# PART1.net
KiCad netlist of a schematic drawn in Altium Designer
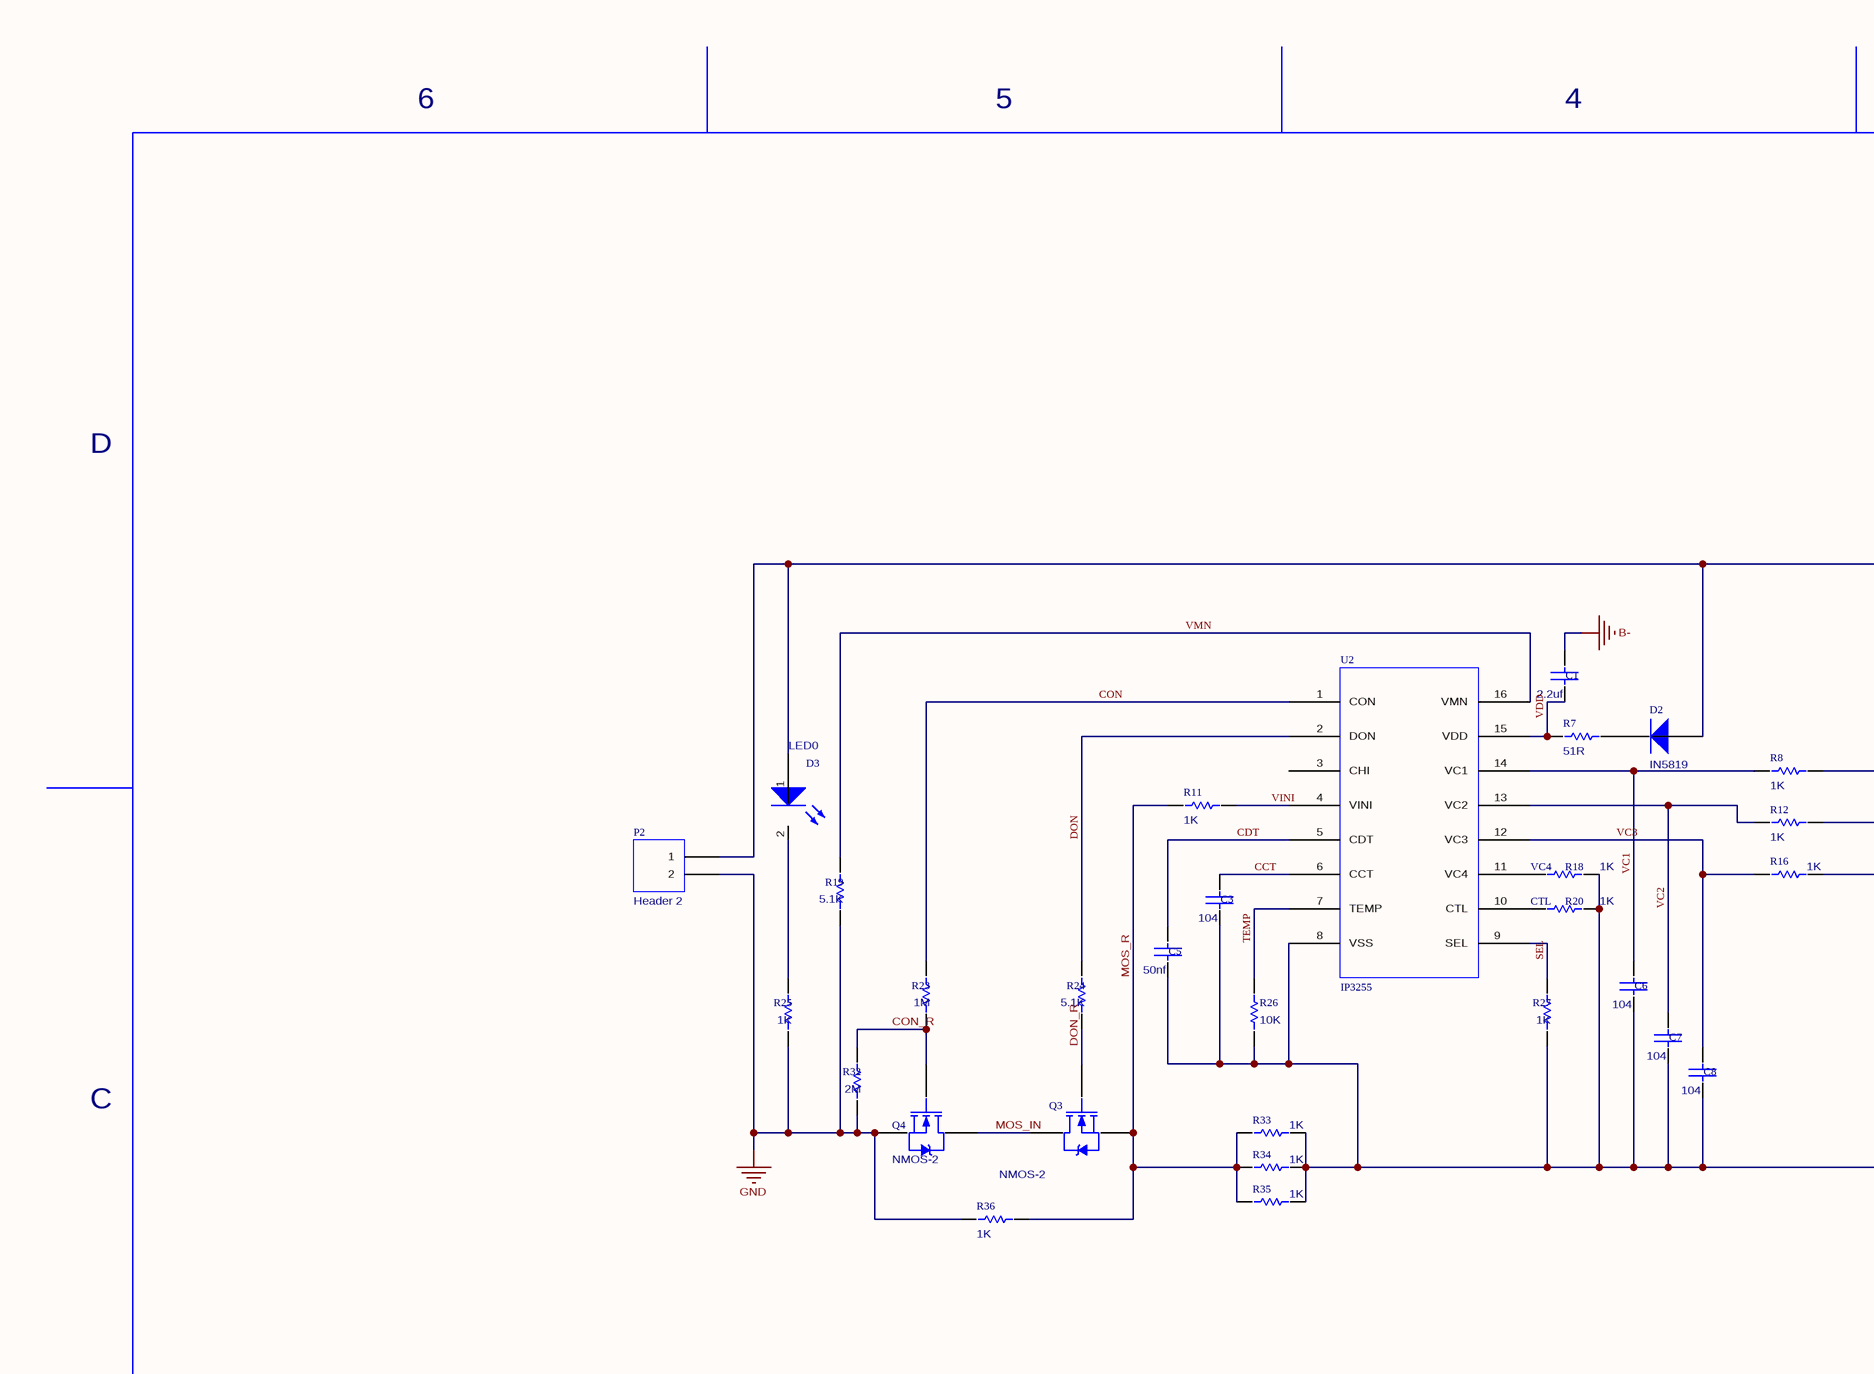
[diagram p0: PART1.SchDoc, top left]
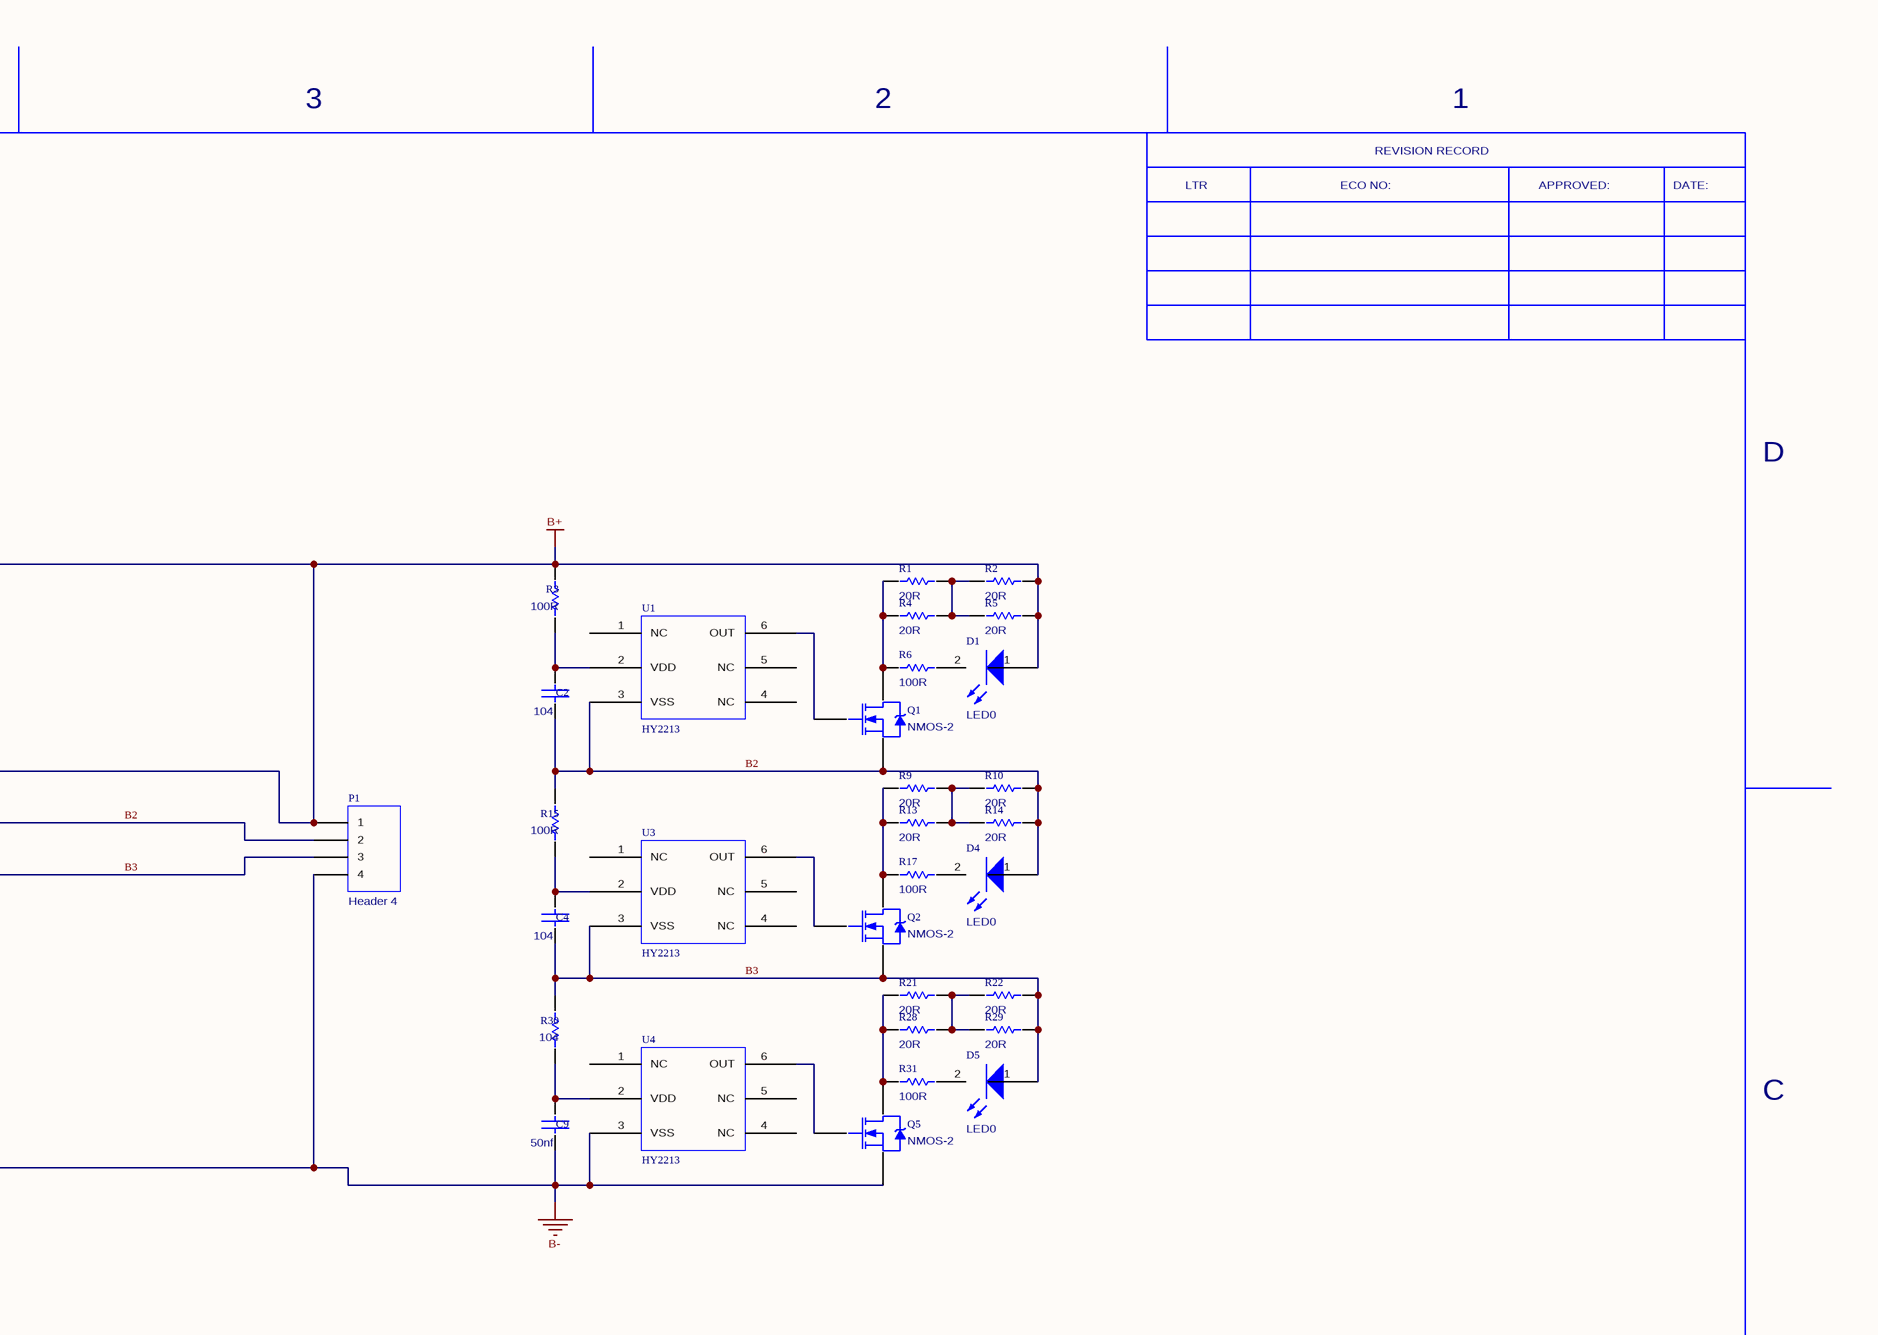
[diagram p1: PART1.SchDoc, top right]
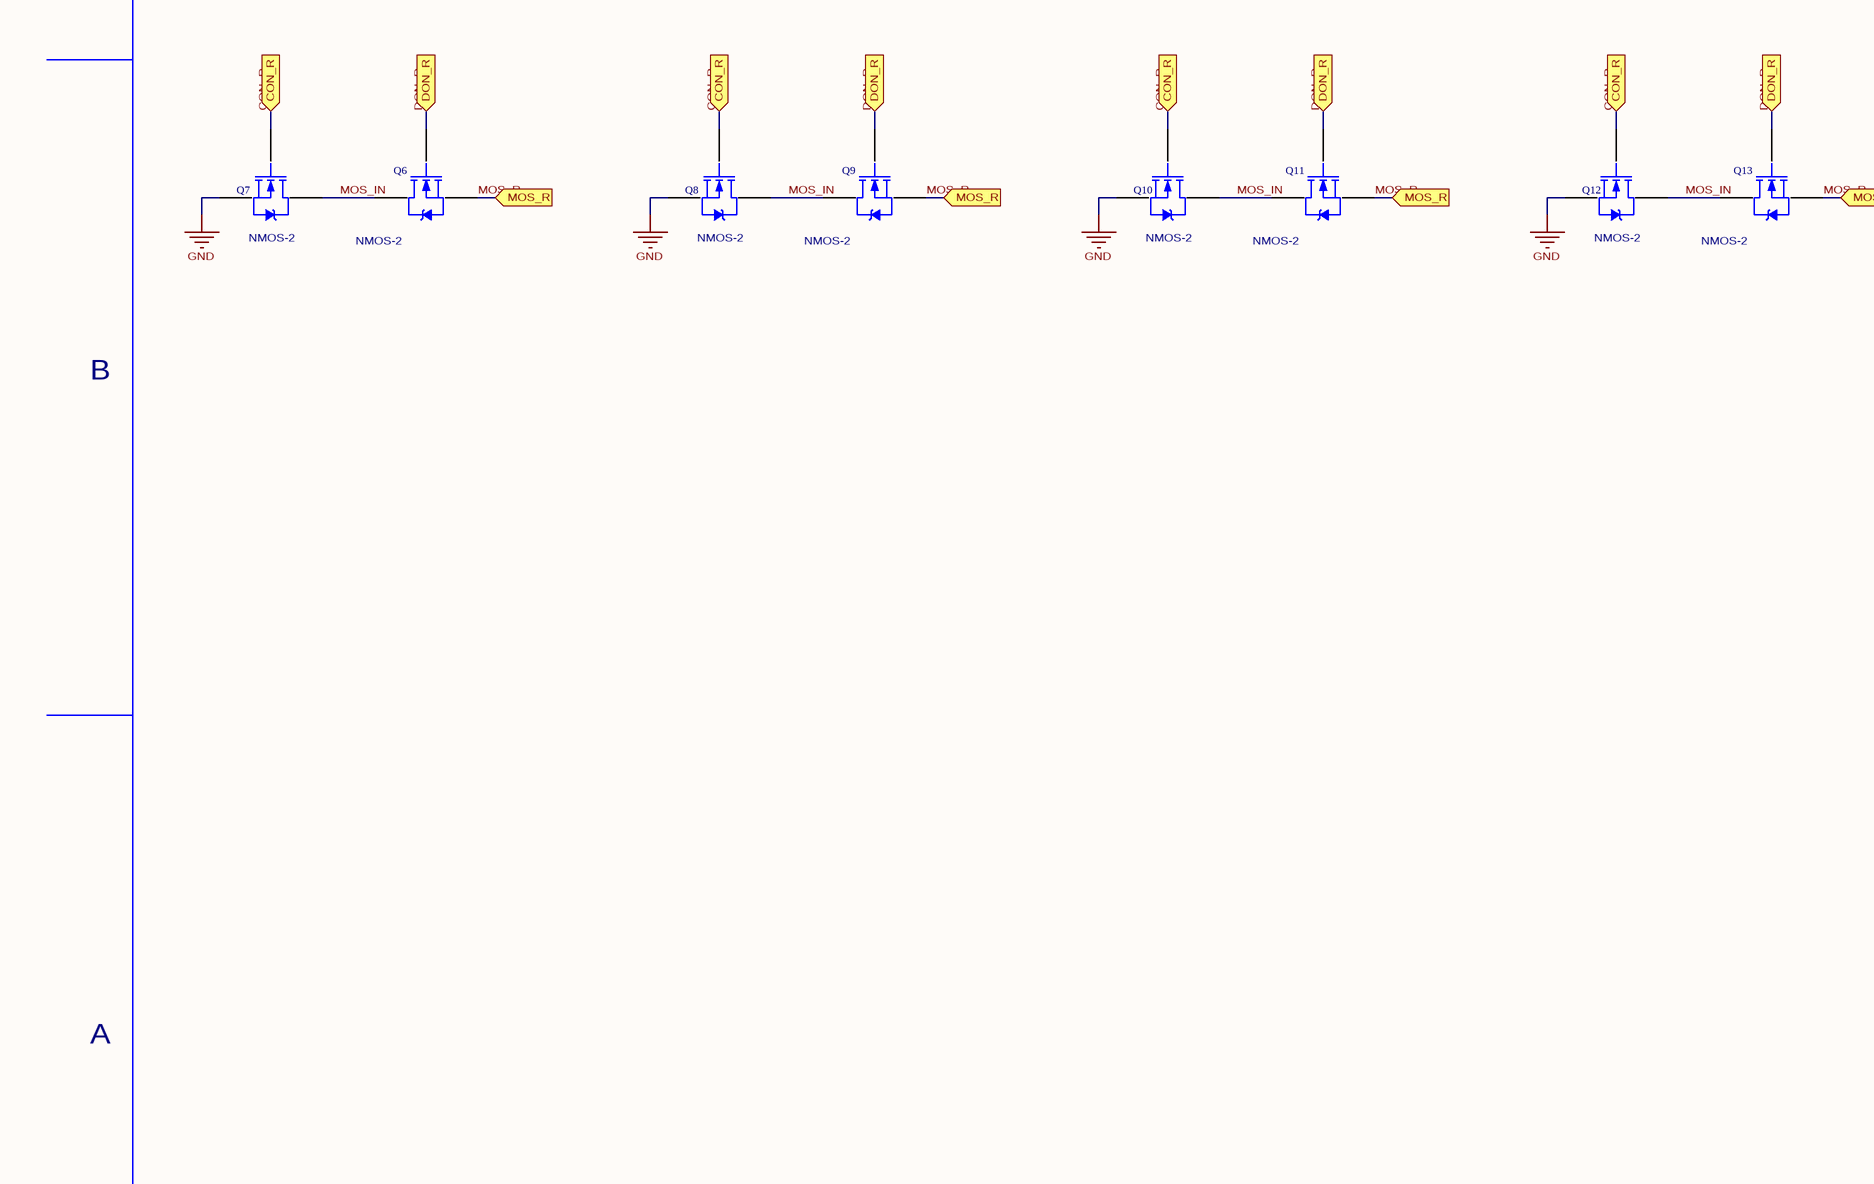
[diagram p2: PART1.SchDoc, bottom left]
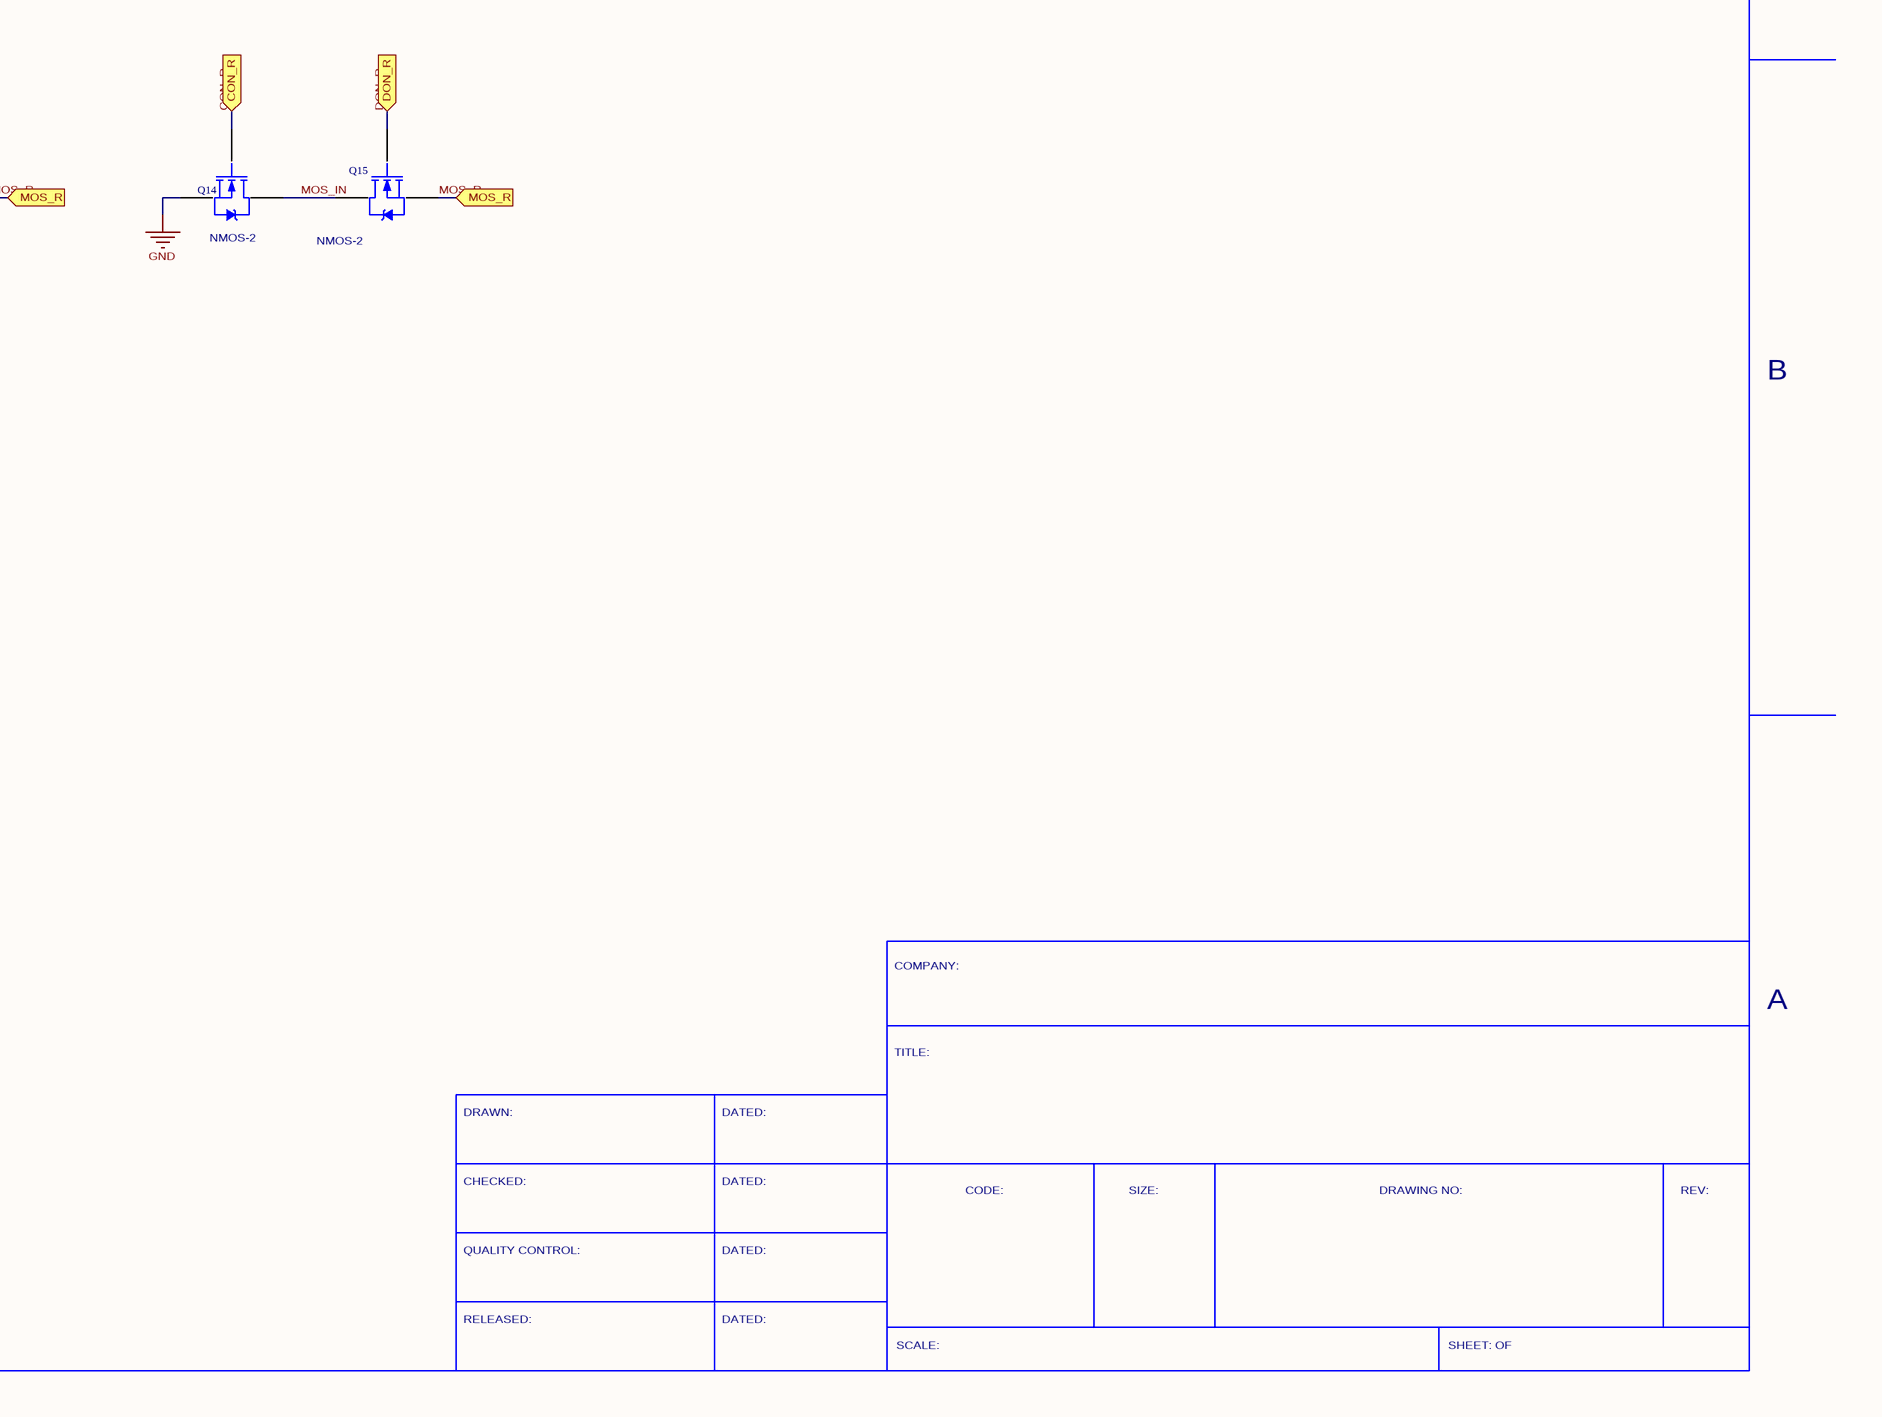
[diagram p3: PART1.SchDoc, bottom right]

(export (version "E")
  (design (tool "Eeschema 10.0.6"))
  (components
    (comp (ref "C1")
      (value "2.2uf")
      (footprint "0805C")
      (description "Capacitor")
      (fields (field (name "Comment") "CAP") (field (name "PUBLISHER") "Altium Limited"))
      (libsource (lib "*") (part "CAP"))
    )
    (comp (ref "C2")
      (value "104")
      (footprint "0603C")
      (description "Capacitor")
      (fields (field (name "Comment") "CAP") (field (name "PUBLISHER") "Altium Limited"))
      (libsource (lib "*") (part "CAP"))
    )
    (comp (ref "C3")
      (value "104")
      (footprint "0805C")
      (description "Capacitor")
      (fields (field (name "Comment") "CAP") (field (name "PUBLISHER") "Altium Limited"))
      (libsource (lib "*") (part "CAP"))
    )
    (comp (ref "C4")
      (value "104")
      (footprint "0603C")
      (description "Capacitor")
      (fields (field (name "Comment") "CAP") (field (name "PUBLISHER") "Altium Limited"))
      (libsource (lib "*") (part "CAP"))
    )
    (comp (ref "C5")
      (value "50nf")
      (footprint "0805C")
      (description "Capacitor")
      (fields (field (name "Comment") "CAP") (field (name "PUBLISHER") "Altium Limited"))
      (libsource (lib "*") (part "CAP"))
    )
    (comp (ref "C6")
      (value "104")
      (footprint "0603C")
      (description "Capacitor")
      (fields (field (name "Comment") "CAP") (field (name "PUBLISHER") "Altium Limited"))
      (libsource (lib "*") (part "CAP"))
    )
    (comp (ref "C7")
      (value "104")
      (footprint "0603C")
      (description "Capacitor")
      (fields (field (name "Comment") "CAP") (field (name "PUBLISHER") "Altium Limited"))
      (libsource (lib "*") (part "CAP"))
    )
    (comp (ref "C8")
      (value "104")
      (footprint "0603C")
      (description "Capacitor")
      (fields (field (name "Comment") "CAP") (field (name "PUBLISHER") "Altium Limited"))
      (libsource (lib "*") (part "CAP"))
    )
    (comp (ref "C9")
      (value "50nf")
      (footprint "0603C")
      (description "Capacitor")
      (fields (field (name "Comment") "CAP") (field (name "PUBLISHER") "Altium Limited"))
      (libsource (lib "*") (part "CAP"))
    )
    (comp (ref "D1")
      (value "LED0")
      (footprint "0805D")
      (description "Typical INFRARED GaAs LED")
      (fields (field (name "PUBLISHER") "Altium Limited"))
      (libsource (lib "*") (part "LED0"))
    )
    (comp (ref "D2")
      (value "DIODE_1N4001")
      (footprint "SOD123")
      (description "1 Amp General Purpose Rectifier")
      (fields (field (name "PUBLISHER") "Altium Limited"))
      (libsource (lib "*") (part "DIODE_1N4001"))
    )
    (comp (ref "D3")
      (value "LED0")
      (footprint "0805D")
      (description "Typical INFRARED GaAs LED")
      (fields (field (name "PUBLISHER") "Altium Limited"))
      (libsource (lib "*") (part "LED0"))
    )
    (comp (ref "D4")
      (value "LED0")
      (footprint "0805D")
      (description "Typical INFRARED GaAs LED")
      (fields (field (name "PUBLISHER") "Altium Limited"))
      (libsource (lib "*") (part "LED0"))
    )
    (comp (ref "D5")
      (value "LED0")
      (footprint "0805D")
      (description "Typical INFRARED GaAs LED")
      (fields (field (name "PUBLISHER") "Altium Limited"))
      (libsource (lib "*") (part "LED0"))
    )
    (comp (ref "P1")
      (value "HEADER_4")
      (footprint "2.54/4PM")
      (description "Header, 4-Pin")
      (fields (field (name "PUBLISHER") "Altium Limited"))
      (libsource (lib "*") (part "HEADER_4"))
    )
    (comp (ref "P2")
      (value "HEADER_2")
      (footprint "KF127_2")
      (description "Header, 2-Pin")
      (fields (field (name "PUBLISHER") "Altium Limited"))
      (libsource (lib "*") (part "HEADER_2"))
    )
    (comp (ref "Q1")
      (value "NMOS-2_2")
      (footprint "SOT23-3")
      (description "N-Channel Power MOSFET")
      (fields (field (name "PUBLISHER") "Altium Limited"))
      (libsource (lib "*") (part "NMOS-2_2"))
    )
    (comp (ref "Q2")
      (value "NMOS-2_2")
      (footprint "SOT23-3")
      (description "N-Channel Power MOSFET")
      (fields (field (name "PUBLISHER") "Altium Limited"))
      (libsource (lib "*") (part "NMOS-2_2"))
    )
    (comp (ref "Q3")
      (value "NMOS-2")
      (footprint "TO252-3")
      (description "N-Channel Power MOSFET")
      (fields (field (name "PUBLISHER") "Altium Limited"))
      (libsource (lib "*") (part "NMOS-2"))
    )
    (comp (ref "Q4")
      (value "NMOS-2")
      (footprint "TO252-3")
      (description "N-Channel Power MOSFET")
      (fields (field (name "PUBLISHER") "Altium Limited"))
      (libsource (lib "*") (part "NMOS-2"))
    )
    (comp (ref "Q5")
      (value "NMOS-2_2")
      (footprint "SOT23-3")
      (description "N-Channel Power MOSFET")
      (fields (field (name "PUBLISHER") "Altium Limited"))
      (libsource (lib "*") (part "NMOS-2_2"))
    )
    (comp (ref "Q6")
      (value "NMOS-2")
      (footprint "TO252-3")
      (description "N-Channel Power MOSFET")
      (fields (field (name "PUBLISHER") "Altium Limited"))
      (libsource (lib "*") (part "NMOS-2"))
    )
    (comp (ref "Q7")
      (value "NMOS-2")
      (footprint "TO252-3")
      (description "N-Channel Power MOSFET")
      (fields (field (name "PUBLISHER") "Altium Limited"))
      (libsource (lib "*") (part "NMOS-2"))
    )
    (comp (ref "Q8")
      (value "NMOS-2")
      (footprint "TO252-3")
      (description "N-Channel Power MOSFET")
      (fields (field (name "PUBLISHER") "Altium Limited"))
      (libsource (lib "*") (part "NMOS-2"))
    )
    (comp (ref "Q9")
      (value "NMOS-2")
      (footprint "TO252-3")
      (description "N-Channel Power MOSFET")
      (fields (field (name "PUBLISHER") "Altium Limited"))
      (libsource (lib "*") (part "NMOS-2"))
    )
    (comp (ref "Q10")
      (value "NMOS-2")
      (footprint "TO252-3")
      (description "N-Channel Power MOSFET")
      (fields (field (name "PUBLISHER") "Altium Limited"))
      (libsource (lib "*") (part "NMOS-2"))
    )
    (comp (ref "Q11")
      (value "NMOS-2")
      (footprint "TO252-3")
      (description "N-Channel Power MOSFET")
      (fields (field (name "PUBLISHER") "Altium Limited"))
      (libsource (lib "*") (part "NMOS-2"))
    )
    (comp (ref "Q12")
      (value "NMOS-2")
      (footprint "TO252-3")
      (description "N-Channel Power MOSFET")
      (fields (field (name "PUBLISHER") "Altium Limited"))
      (libsource (lib "*") (part "NMOS-2"))
    )
    (comp (ref "Q13")
      (value "NMOS-2")
      (footprint "TO252-3")
      (description "N-Channel Power MOSFET")
      (fields (field (name "PUBLISHER") "Altium Limited"))
      (libsource (lib "*") (part "NMOS-2"))
    )
    (comp (ref "Q14")
      (value "NMOS-2")
      (footprint "TO252-3")
      (description "N-Channel Power MOSFET")
      (fields (field (name "PUBLISHER") "Altium Limited"))
      (libsource (lib "*") (part "NMOS-2"))
    )
    (comp (ref "Q15")
      (value "NMOS-2")
      (footprint "TO252-3")
      (description "N-Channel Power MOSFET")
      (fields (field (name "PUBLISHER") "Altium Limited"))
      (libsource (lib "*") (part "NMOS-2"))
    )
    (comp (ref "R1")
      (value "20R")
      (footprint "1206C")
      (description "Semiconductor Resistor")
      (fields (field (name "Comment") "RES_SEMI") (field (name "PUBLISHER") "Altium Limited"))
      (libsource (lib "*") (part "RES_SEMI"))
    )
    (comp (ref "R2")
      (value "20R")
      (footprint "1206C")
      (description "Semiconductor Resistor")
      (fields (field (name "Comment") "RES_SEMI") (field (name "PUBLISHER") "Altium Limited"))
      (libsource (lib "*") (part "RES_SEMI"))
    )
    (comp (ref "R3")
      (value "100R")
      (footprint "0603R")
      (description "Semiconductor Resistor")
      (fields (field (name "Comment") "RES_SEMI") (field (name "PUBLISHER") "Altium Limited"))
      (libsource (lib "*") (part "RES_SEMI"))
    )
    (comp (ref "R4")
      (value "20R")
      (footprint "1206C")
      (description "Semiconductor Resistor")
      (fields (field (name "Comment") "RES_SEMI") (field (name "PUBLISHER") "Altium Limited"))
      (libsource (lib "*") (part "RES_SEMI"))
    )
    (comp (ref "R5")
      (value "20R")
      (footprint "1206C")
      (description "Semiconductor Resistor")
      (fields (field (name "Comment") "RES_SEMI") (field (name "PUBLISHER") "Altium Limited"))
      (libsource (lib "*") (part "RES_SEMI"))
    )
    (comp (ref "R6")
      (value "100R")
      (footprint "0805R")
      (description "Semiconductor Resistor")
      (fields (field (name "Comment") "RES_SEMI") (field (name "PUBLISHER") "Altium Limited"))
      (libsource (lib "*") (part "RES_SEMI"))
    )
    (comp (ref "R7")
      (value "51R")
      (footprint "0805R")
      (description "Semiconductor Resistor")
      (fields (field (name "Comment") "RES_SEMI") (field (name "PUBLISHER") "Altium Limited"))
      (libsource (lib "*") (part "RES_SEMI"))
    )
    (comp (ref "R8")
      (value "1K")
      (footprint "0603R")
      (description "Semiconductor Resistor")
      (fields (field (name "Comment") "RES_SEMI") (field (name "PUBLISHER") "Altium Limited"))
      (libsource (lib "*") (part "RES_SEMI"))
    )
    (comp (ref "R9")
      (value "20R")
      (footprint "1206C")
      (description "Semiconductor Resistor")
      (fields (field (name "Comment") "RES_SEMI") (field (name "PUBLISHER") "Altium Limited"))
      (libsource (lib "*") (part "RES_SEMI"))
    )
    (comp (ref "R10")
      (value "20R")
      (footprint "1206C")
      (description "Semiconductor Resistor")
      (fields (field (name "Comment") "RES_SEMI") (field (name "PUBLISHER") "Altium Limited"))
      (libsource (lib "*") (part "RES_SEMI"))
    )
    (comp (ref "R11")
      (value "1K")
      (footprint "0805R")
      (description "Semiconductor Resistor")
      (fields (field (name "Comment") "RES_SEMI") (field (name "PUBLISHER") "Altium Limited"))
      (libsource (lib "*") (part "RES_SEMI"))
    )
    (comp (ref "R12")
      (value "1K")
      (footprint "0603R")
      (description "Semiconductor Resistor")
      (fields (field (name "Comment") "RES_SEMI") (field (name "PUBLISHER") "Altium Limited"))
      (libsource (lib "*") (part "RES_SEMI"))
    )
    (comp (ref "R13")
      (value "20R")
      (footprint "1206C")
      (description "Semiconductor Resistor")
      (fields (field (name "Comment") "RES_SEMI") (field (name "PUBLISHER") "Altium Limited"))
      (libsource (lib "*") (part "RES_SEMI"))
    )
    (comp (ref "R14")
      (value "20R")
      (footprint "1206C")
      (description "Semiconductor Resistor")
      (fields (field (name "Comment") "RES_SEMI") (field (name "PUBLISHER") "Altium Limited"))
      (libsource (lib "*") (part "RES_SEMI"))
    )
    (comp (ref "R15")
      (value "100R")
      (footprint "0603R")
      (description "Semiconductor Resistor")
      (fields (field (name "Comment") "RES_SEMI") (field (name "PUBLISHER") "Altium Limited"))
      (libsource (lib "*") (part "RES_SEMI"))
    )
    (comp (ref "R16")
      (value "1K")
      (footprint "0603R")
      (description "Semiconductor Resistor")
      (fields (field (name "Comment") "RES_SEMI") (field (name "PUBLISHER") "Altium Limited"))
      (libsource (lib "*") (part "RES_SEMI"))
    )
    (comp (ref "R17")
      (value "100R")
      (footprint "0805R")
      (description "Semiconductor Resistor")
      (fields (field (name "Comment") "RES_SEMI") (field (name "PUBLISHER") "Altium Limited"))
      (libsource (lib "*") (part "RES_SEMI"))
    )
    (comp (ref "R18")
      (value "1K")
      (footprint "0805R")
      (description "Semiconductor Resistor")
      (fields (field (name "Comment") "RES_SEMI") (field (name "PUBLISHER") "Altium Limited"))
      (libsource (lib "*") (part "RES_SEMI"))
    )
    (comp (ref "R19")
      (value "5.1K")
      (footprint "0805R")
      (description "Semiconductor Resistor")
      (fields (field (name "Comment") "RES_SEMI") (field (name "PUBLISHER") "Altium Limited"))
      (libsource (lib "*") (part "RES_SEMI"))
    )
    (comp (ref "R20")
      (value "1K")
      (footprint "0805R")
      (description "Semiconductor Resistor")
      (fields (field (name "Comment") "RES_SEMI") (field (name "PUBLISHER") "Altium Limited"))
      (libsource (lib "*") (part "RES_SEMI"))
    )
    (comp (ref "R21")
      (value "20R")
      (footprint "1206C")
      (description "Semiconductor Resistor")
      (fields (field (name "Comment") "RES_SEMI") (field (name "PUBLISHER") "Altium Limited"))
      (libsource (lib "*") (part "RES_SEMI"))
    )
    (comp (ref "R22")
      (value "20R")
      (footprint "1206C")
      (description "Semiconductor Resistor")
      (fields (field (name "Comment") "RES_SEMI") (field (name "PUBLISHER") "Altium Limited"))
      (libsource (lib "*") (part "RES_SEMI"))
    )
    (comp (ref "R23")
      (value "1M")
      (footprint "0805R")
      (description "Semiconductor Resistor")
      (fields (field (name "Comment") "RES_SEMI") (field (name "PUBLISHER") "Altium Limited"))
      (libsource (lib "*") (part "RES_SEMI"))
    )
    (comp (ref "R24")
      (value "5.1K")
      (footprint "0805R")
      (description "Semiconductor Resistor")
      (fields (field (name "Comment") "RES_SEMI") (field (name "PUBLISHER") "Altium Limited"))
      (libsource (lib "*") (part "RES_SEMI"))
    )
    (comp (ref "R25")
      (value "1K")
      (footprint "0805R")
      (description "Semiconductor Resistor")
      (fields (field (name "Comment") "RES_SEMI") (field (name "PUBLISHER") "Altium Limited"))
      (libsource (lib "*") (part "RES_SEMI"))
    )
    (comp (ref "R26")
      (value "10K")
      (footprint "0805R")
      (description "Semiconductor Resistor")
      (fields (field (name "Comment") "RES_SEMI") (field (name "PUBLISHER") "Altium Limited"))
      (libsource (lib "*") (part "RES_SEMI"))
    )
    (comp (ref "R27")
      (value "1K")
      (footprint "0805R")
      (description "Semiconductor Resistor")
      (fields (field (name "Comment") "RES_SEMI") (field (name "PUBLISHER") "Altium Limited"))
      (libsource (lib "*") (part "RES_SEMI"))
    )
    (comp (ref "R28")
      (value "20R")
      (footprint "1206C")
      (description "Semiconductor Resistor")
      (fields (field (name "Comment") "RES_SEMI") (field (name "PUBLISHER") "Altium Limited"))
      (libsource (lib "*") (part "RES_SEMI"))
    )
    (comp (ref "R29")
      (value "20R")
      (footprint "1206C")
      (description "Semiconductor Resistor")
      (fields (field (name "Comment") "RES_SEMI") (field (name "PUBLISHER") "Altium Limited"))
      (libsource (lib "*") (part "RES_SEMI"))
    )
    (comp (ref "R30")
      (value "104")
      (footprint "0603R")
      (description "Semiconductor Resistor")
      (fields (field (name "Comment") "RES_SEMI") (field (name "PUBLISHER") "Altium Limited"))
      (libsource (lib "*") (part "RES_SEMI"))
    )
    (comp (ref "R31")
      (value "100R")
      (footprint "0805R")
      (description "Semiconductor Resistor")
      (fields (field (name "Comment") "RES_SEMI") (field (name "PUBLISHER") "Altium Limited"))
      (libsource (lib "*") (part "RES_SEMI"))
    )
    (comp (ref "R32")
      (value "2M")
      (footprint "0805R")
      (description "Semiconductor Resistor")
      (fields (field (name "Comment") "RES_SEMI") (field (name "PUBLISHER") "Altium Limited"))
      (libsource (lib "*") (part "RES_SEMI"))
    )
    (comp (ref "R33")
      (value "1K")
      (footprint "3920R")
      (description "Semiconductor Resistor")
      (fields (field (name "Comment") "RES_SEMI") (field (name "PUBLISHER") "Altium Limited"))
      (libsource (lib "*") (part "RES_SEMI"))
    )
    (comp (ref "R34")
      (value "1K")
      (footprint "3920R")
      (description "Semiconductor Resistor")
      (fields (field (name "Comment") "RES_SEMI") (field (name "PUBLISHER") "Altium Limited"))
      (libsource (lib "*") (part "RES_SEMI"))
    )
    (comp (ref "R35")
      (value "1K")
      (footprint "3920R")
      (description "Semiconductor Resistor")
      (fields (field (name "Comment") "RES_SEMI") (field (name "PUBLISHER") "Altium Limited"))
      (libsource (lib "*") (part "RES_SEMI"))
    )
    (comp (ref "R36")
      (value "1K")
      (footprint "0805R")
      (description "Semiconductor Resistor")
      (fields (field (name "Comment") "RES_SEMI") (field (name "PUBLISHER") "Altium Limited"))
      (libsource (lib "*") (part "RES_SEMI"))
    )
    (comp (ref "U1") (value "HY2213") (footprint "SOT23-6") (libsource (lib "*") (part "HY2213")))
    (comp (ref "U2") (value "IP3255") (footprint "TSSOP16-OR65-4R40") (libsource (lib "*") (part "IP3255")))
    (comp (ref "U3") (value "HY2213") (footprint "SOT23-6") (libsource (lib "*") (part "HY2213")))
    (comp (ref "U4") (value "HY2213") (footprint "SOT23-6") (libsource (lib "*") (part "HY2213")))
  )
  (nets
    (net (code "1") (name "/B2") (class "Default")
      (node (ref "C2") (pin "1") (pinfunction "1_1") (pintype "passive"))
      (node (ref "D4") (pin "1") (pinfunction "A_1") (pintype "passive"))
      (node (ref "P1") (pin "2") (pinfunction "2_2") (pintype "passive"))
      (node (ref "Q1") (pin "2") (pinfunction "S_2") (pintype "passive"))
      (node (ref "R10") (pin "2") (pinfunction "2_2") (pintype "passive"))
      (node (ref "R12") (pin "2") (pinfunction "2_2") (pintype "passive"))
      (node (ref "R14") (pin "2") (pinfunction "2_2") (pintype "passive"))
      (node (ref "R15") (pin "2") (pinfunction "2_2") (pintype "passive"))
      (node (ref "U1") (pin "3") (pinfunction "VSS_3") (pintype "passive"))
    )
    (net (code "2") (name "/B3") (class "Default")
      (node (ref "C4") (pin "1") (pinfunction "1_1") (pintype "passive"))
      (node (ref "D5") (pin "1") (pinfunction "A_1") (pintype "passive"))
      (node (ref "P1") (pin "3") (pinfunction "3_3") (pintype "passive"))
      (node (ref "Q2") (pin "2") (pinfunction "S_2") (pintype "passive"))
      (node (ref "R16") (pin "1") (pinfunction "1_1") (pintype "passive"))
      (node (ref "R22") (pin "2") (pinfunction "2_2") (pintype "passive"))
      (node (ref "R29") (pin "2") (pinfunction "2_2") (pintype "passive"))
      (node (ref "R30") (pin "2") (pinfunction "2_2") (pintype "passive"))
      (node (ref "U3") (pin "3") (pinfunction "VSS_3") (pintype "passive"))
    )
    (net (code "3") (name "/CCT") (class "Default")
      (node (ref "C3") (pin "2") (pinfunction "2_2") (pintype "passive"))
      (node (ref "U2") (pin "6") (pinfunction "CCT_6") (pintype "passive"))
    )
    (net (code "4") (name "/CDT") (class "Default")
      (node (ref "C5") (pin "2") (pinfunction "2_2") (pintype "passive"))
      (node (ref "U2") (pin "5") (pinfunction "CDT_5") (pintype "passive"))
    )
    (net (code "5") (name "/CON") (class "Default")
      (node (ref "R23") (pin "2") (pinfunction "2_2") (pintype "passive"))
      (node (ref "U2") (pin "1") (pinfunction "CON_1") (pintype "passive"))
    )
    (net (code "6") (name "/CON_R") (class "Default")
      (node (ref "Q10") (pin "1") (pinfunction "G_1") (pintype "passive"))
      (node (ref "Q12") (pin "1") (pinfunction "G_1") (pintype "passive"))
      (node (ref "Q14") (pin "1") (pinfunction "G_1") (pintype "passive"))
      (node (ref "Q4") (pin "1") (pinfunction "G_1") (pintype "passive"))
      (node (ref "Q7") (pin "1") (pinfunction "G_1") (pintype "passive"))
      (node (ref "Q8") (pin "1") (pinfunction "G_1") (pintype "passive"))
      (node (ref "R23") (pin "1") (pinfunction "1_1") (pintype "passive"))
      (node (ref "R32") (pin "2") (pinfunction "2_2") (pintype "passive"))
    )
    (net (code "7") (name "/DON") (class "Default")
      (node (ref "R24") (pin "2") (pinfunction "2_2") (pintype "passive"))
      (node (ref "U2") (pin "2") (pinfunction "DON_2") (pintype "passive"))
    )
    (net (code "8") (name "/DON_R") (class "Default")
      (node (ref "Q11") (pin "1") (pinfunction "G_1") (pintype "passive"))
      (node (ref "Q13") (pin "1") (pinfunction "G_1") (pintype "passive"))
      (node (ref "Q15") (pin "1") (pinfunction "G_1") (pintype "passive"))
      (node (ref "Q3") (pin "1") (pinfunction "G_1") (pintype "passive"))
      (node (ref "Q6") (pin "1") (pinfunction "G_1") (pintype "passive"))
      (node (ref "Q9") (pin "1") (pinfunction "G_1") (pintype "passive"))
      (node (ref "R24") (pin "1") (pinfunction "1_1") (pintype "passive"))
    )
    (net (code "9") (name "/MOS_IN") (class "Default")
      (node (ref "Q10") (pin "2") (pinfunction "D_2") (pintype "passive"))
      (node (ref "Q11") (pin "2") (pinfunction "D_2") (pintype "passive"))
      (node (ref "Q12") (pin "2") (pinfunction "D_2") (pintype "passive"))
      (node (ref "Q13") (pin "2") (pinfunction "D_2") (pintype "passive"))
      (node (ref "Q14") (pin "2") (pinfunction "D_2") (pintype "passive"))
      (node (ref "Q15") (pin "2") (pinfunction "D_2") (pintype "passive"))
      (node (ref "Q3") (pin "2") (pinfunction "D_2") (pintype "passive"))
      (node (ref "Q4") (pin "2") (pinfunction "D_2") (pintype "passive"))
      (node (ref "Q6") (pin "2") (pinfunction "D_2") (pintype "passive"))
      (node (ref "Q7") (pin "2") (pinfunction "D_2") (pintype "passive"))
      (node (ref "Q8") (pin "2") (pinfunction "D_2") (pintype "passive"))
      (node (ref "Q9") (pin "2") (pinfunction "D_2") (pintype "passive"))
    )
    (net (code "10") (name "/MOS_R") (class "Default")
      (node (ref "Q11") (pin "3") (pinfunction "S_3") (pintype "passive"))
      (node (ref "Q13") (pin "3") (pinfunction "S_3") (pintype "passive"))
      (node (ref "Q15") (pin "3") (pinfunction "S_3") (pintype "passive"))
      (node (ref "Q3") (pin "3") (pinfunction "S_3") (pintype "passive"))
      (node (ref "Q6") (pin "3") (pinfunction "S_3") (pintype "passive"))
      (node (ref "Q9") (pin "3") (pinfunction "S_3") (pintype "passive"))
      (node (ref "R11") (pin "2") (pinfunction "2_2") (pintype "passive"))
      (node (ref "R33") (pin "1") (pinfunction "1_1") (pintype "passive"))
      (node (ref "R34") (pin "1") (pinfunction "1_1") (pintype "passive"))
      (node (ref "R35") (pin "1") (pinfunction "1_1") (pintype "passive"))
      (node (ref "R36") (pin "1") (pinfunction "1_1") (pintype "passive"))
    )
    (net (code "11") (name "/SEL") (class "Default")
      (node (ref "R27") (pin "2") (pinfunction "2_2") (pintype "passive"))
      (node (ref "U2") (pin "9") (pinfunction "SEL_9") (pintype "passive"))
    )
    (net (code "12") (name "/TEMP") (class "Default")
      (node (ref "R26") (pin "1") (pinfunction "1_1") (pintype "passive"))
      (node (ref "U2") (pin "7") (pinfunction "TEMP_7") (pintype "passive"))
    )
    (net (code "13") (name "/VC1") (class "Default")
      (node (ref "C6") (pin "2") (pinfunction "2_2") (pintype "passive"))
      (node (ref "R8") (pin "1") (pinfunction "1_1") (pintype "passive"))
      (node (ref "U2") (pin "14") (pinfunction "VC1_14") (pintype "passive"))
    )
    (net (code "14") (name "/VC2") (class "Default")
      (node (ref "C7") (pin "2") (pinfunction "2_2") (pintype "passive"))
      (node (ref "R12") (pin "1") (pinfunction "1_1") (pintype "passive"))
      (node (ref "U2") (pin "13") (pinfunction "VC2_13") (pintype "passive"))
    )
    (net (code "15") (name "/VC3") (class "Default")
      (node (ref "C8") (pin "2") (pinfunction "2_2") (pintype "passive"))
      (node (ref "R16") (pin "2") (pinfunction "2_2") (pintype "passive"))
      (node (ref "U2") (pin "12") (pinfunction "VC3_12") (pintype "passive"))
    )
    (net (code "16") (name "/VDD") (class "Default")
      (node (ref "C1") (pin "1") (pinfunction "1_1") (pintype "passive"))
      (node (ref "R7") (pin "1") (pinfunction "1_1") (pintype "passive"))
      (node (ref "U2") (pin "15") (pinfunction "VDD_15") (pintype "passive"))
    )
    (net (code "17") (name "/VINI") (class "Default")
      (node (ref "R11") (pin "1") (pinfunction "1_1") (pintype "passive"))
      (node (ref "U2") (pin "4") (pinfunction "VINI_4") (pintype "passive"))
    )
    (net (code "18") (name "/VMN") (class "Default")
      (node (ref "R19") (pin "2") (pinfunction "2_2") (pintype "passive"))
      (node (ref "U2") (pin "16") (pinfunction "VMN_16") (pintype "passive"))
    )
    (net (code "19") (name "B+") (class "Default")
      (node (ref "D1") (pin "1") (pinfunction "A_1") (pintype "passive"))
      (node (ref "D2") (pin "1") (pinfunction "A_1") (pintype "passive"))
      (node (ref "D3") (pin "1") (pinfunction "A_1") (pintype "passive"))
      (node (ref "P1") (pin "1") (pinfunction "1_1") (pintype "passive"))
      (node (ref "P2") (pin "1") (pinfunction "1_1") (pintype "passive"))
      (node (ref "R2") (pin "2") (pinfunction "2_2") (pintype "passive"))
      (node (ref "R3") (pin "2") (pinfunction "2_2") (pintype "passive"))
      (node (ref "R5") (pin "2") (pinfunction "2_2") (pintype "passive"))
      (node (ref "R8") (pin "2") (pinfunction "2_2") (pintype "passive"))
    )
    (net (code "20") (name "B-") (class "Default")
      (node (ref "C1") (pin "2") (pinfunction "2_2") (pintype "passive"))
      (node (ref "C3") (pin "1") (pinfunction "1_1") (pintype "passive"))
      (node (ref "C5") (pin "1") (pinfunction "1_1") (pintype "passive"))
      (node (ref "C6") (pin "1") (pinfunction "1_1") (pintype "passive"))
      (node (ref "C7") (pin "1") (pinfunction "1_1") (pintype "passive"))
      (node (ref "C8") (pin "1") (pinfunction "1_1") (pintype "passive"))
      (node (ref "C9") (pin "1") (pinfunction "1_1") (pintype "passive"))
      (node (ref "P1") (pin "4") (pinfunction "4_4") (pintype "passive"))
      (node (ref "Q5") (pin "2") (pinfunction "S_2") (pintype "passive"))
      (node (ref "R18") (pin "2") (pinfunction "2_2") (pintype "passive"))
      (node (ref "R20") (pin "2") (pinfunction "2_2") (pintype "passive"))
      (node (ref "R26") (pin "2") (pinfunction "2_2") (pintype "passive"))
      (node (ref "R27") (pin "1") (pinfunction "1_1") (pintype "passive"))
      (node (ref "R33") (pin "2") (pinfunction "2_2") (pintype "passive"))
      (node (ref "R34") (pin "2") (pinfunction "2_2") (pintype "passive"))
      (node (ref "R35") (pin "2") (pinfunction "2_2") (pintype "passive"))
      (node (ref "U2") (pin "8") (pinfunction "VSS_8") (pintype "passive"))
      (node (ref "U4") (pin "3") (pinfunction "VSS_3") (pintype "passive"))
    )
    (net (code "21") (name "GND") (class "Default")
      (node (ref "P2") (pin "2") (pinfunction "2_2") (pintype "passive"))
      (node (ref "Q10") (pin "3") (pinfunction "S_3") (pintype "passive"))
      (node (ref "Q12") (pin "3") (pinfunction "S_3") (pintype "passive"))
      (node (ref "Q14") (pin "3") (pinfunction "S_3") (pintype "passive"))
      (node (ref "Q4") (pin "3") (pinfunction "S_3") (pintype "passive"))
      (node (ref "Q7") (pin "3") (pinfunction "S_3") (pintype "passive"))
      (node (ref "Q8") (pin "3") (pinfunction "S_3") (pintype "passive"))
      (node (ref "R19") (pin "1") (pinfunction "1_1") (pintype "passive"))
      (node (ref "R25") (pin "1") (pinfunction "1_1") (pintype "passive"))
      (node (ref "R32") (pin "1") (pinfunction "1_1") (pintype "passive"))
      (node (ref "R36") (pin "2") (pinfunction "2_2") (pintype "passive"))
    )
    (net (code "22") (name "Net-(D1-K)") (class "Default")
      (node (ref "D1") (pin "2") (pinfunction "K_2") (pintype "passive"))
      (node (ref "R6") (pin "2") (pinfunction "2_2") (pintype "passive"))
    )
    (net (code "23") (name "Net-(D2-K)") (class "Default")
      (node (ref "D2") (pin "2") (pinfunction "K_2") (pintype "passive"))
      (node (ref "R7") (pin "2") (pinfunction "2_2") (pintype "passive"))
    )
    (net (code "24") (name "Net-(D3-K)") (class "Default")
      (node (ref "D3") (pin "2") (pinfunction "K_2") (pintype "passive"))
      (node (ref "R25") (pin "2") (pinfunction "2_2") (pintype "passive"))
    )
    (net (code "25") (name "Net-(D4-K)") (class "Default")
      (node (ref "D4") (pin "2") (pinfunction "K_2") (pintype "passive"))
      (node (ref "R17") (pin "2") (pinfunction "2_2") (pintype "passive"))
    )
    (net (code "26") (name "Net-(D5-K)") (class "Default")
      (node (ref "D5") (pin "2") (pinfunction "K_2") (pintype "passive"))
      (node (ref "R31") (pin "2") (pinfunction "2_2") (pintype "passive"))
    )
    (net (code "27") (name "Net-(Q1-D)") (class "Default")
      (node (ref "Q1") (pin "3") (pinfunction "D_3") (pintype "passive"))
      (node (ref "R1") (pin "1") (pinfunction "1_1") (pintype "passive"))
      (node (ref "R4") (pin "1") (pinfunction "1_1") (pintype "passive"))
      (node (ref "R6") (pin "1") (pinfunction "1_1") (pintype "passive"))
    )
    (net (code "28") (name "Net-(Q1-G)") (class "Default")
      (node (ref "Q1") (pin "1") (pinfunction "G_1") (pintype "passive"))
      (node (ref "U1") (pin "6") (pinfunction "OUT_6") (pintype "passive"))
    )
    (net (code "29") (name "Net-(Q2-D)") (class "Default")
      (node (ref "Q2") (pin "3") (pinfunction "D_3") (pintype "passive"))
      (node (ref "R13") (pin "1") (pinfunction "1_1") (pintype "passive"))
      (node (ref "R17") (pin "1") (pinfunction "1_1") (pintype "passive"))
      (node (ref "R9") (pin "1") (pinfunction "1_1") (pintype "passive"))
    )
    (net (code "30") (name "Net-(Q2-G)") (class "Default")
      (node (ref "Q2") (pin "1") (pinfunction "G_1") (pintype "passive"))
      (node (ref "U3") (pin "6") (pinfunction "OUT_6") (pintype "passive"))
    )
    (net (code "31") (name "Net-(Q5-D)") (class "Default")
      (node (ref "Q5") (pin "3") (pinfunction "D_3") (pintype "passive"))
      (node (ref "R21") (pin "1") (pinfunction "1_1") (pintype "passive"))
      (node (ref "R28") (pin "1") (pinfunction "1_1") (pintype "passive"))
      (node (ref "R31") (pin "1") (pinfunction "1_1") (pintype "passive"))
    )
    (net (code "32") (name "Net-(Q5-G)") (class "Default")
      (node (ref "Q5") (pin "1") (pinfunction "G_1") (pintype "passive"))
      (node (ref "U4") (pin "6") (pinfunction "OUT_6") (pintype "passive"))
    )
    (net (code "33") (name "Net-(R1-Pad2)") (class "Default")
      (node (ref "R1") (pin "2") (pinfunction "2_2") (pintype "passive"))
      (node (ref "R2") (pin "1") (pinfunction "1_1") (pintype "passive"))
      (node (ref "R4") (pin "2") (pinfunction "2_2") (pintype "passive"))
      (node (ref "R5") (pin "1") (pinfunction "1_1") (pintype "passive"))
    )
    (net (code "34") (name "Net-(R10-Pad1)") (class "Default")
      (node (ref "R10") (pin "1") (pinfunction "1_1") (pintype "passive"))
      (node (ref "R13") (pin "2") (pinfunction "2_2") (pintype "passive"))
      (node (ref "R14") (pin "1") (pinfunction "1_1") (pintype "passive"))
      (node (ref "R9") (pin "2") (pinfunction "2_2") (pintype "passive"))
    )
    (net (code "35") (name "Net-(R21-Pad2)") (class "Default")
      (node (ref "R21") (pin "2") (pinfunction "2_2") (pintype "passive"))
      (node (ref "R22") (pin "1") (pinfunction "1_1") (pintype "passive"))
      (node (ref "R28") (pin "2") (pinfunction "2_2") (pintype "passive"))
      (node (ref "R29") (pin "1") (pinfunction "1_1") (pintype "passive"))
    )
    (net (code "36") (name "Net-(U1-VDD)") (class "Default")
      (node (ref "C2") (pin "2") (pinfunction "2_2") (pintype "passive"))
      (node (ref "R3") (pin "1") (pinfunction "1_1") (pintype "passive"))
      (node (ref "U1") (pin "2") (pinfunction "VDD_2") (pintype "passive"))
    )
    (net (code "37") (name "Net-(U2-CTL)") (class "Default")
      (node (ref "R20") (pin "1") (pinfunction "1_1") (pintype "passive"))
      (node (ref "U2") (pin "10") (pinfunction "CTL_10") (pintype "passive"))
    )
    (net (code "38") (name "Net-(U2-VC4)") (class "Default")
      (node (ref "R18") (pin "1") (pinfunction "1_1") (pintype "passive"))
      (node (ref "U2") (pin "11") (pinfunction "VC4_11") (pintype "passive"))
    )
    (net (code "39") (name "Net-(U3-VDD)") (class "Default")
      (node (ref "C4") (pin "2") (pinfunction "2_2") (pintype "passive"))
      (node (ref "R15") (pin "1") (pinfunction "1_1") (pintype "passive"))
      (node (ref "U3") (pin "2") (pinfunction "VDD_2") (pintype "passive"))
    )
    (net (code "40") (name "Net-(U4-VDD)") (class "Default")
      (node (ref "C9") (pin "2") (pinfunction "2_2") (pintype "passive"))
      (node (ref "R30") (pin "1") (pinfunction "1_1") (pintype "passive"))
      (node (ref "U4") (pin "2") (pinfunction "VDD_2") (pintype "passive"))
    )
    (net (code "41") (name "unconnected-(U1-NC-Pad1)") (class "Default")
      (node (ref "U1") (pin "1") (pinfunction "NC_1") (pintype "passive"))
    )
    (net (code "42") (name "unconnected-(U1-NC-Pad4)") (class "Default")
      (node (ref "U1") (pin "4") (pinfunction "NC_4") (pintype "passive"))
    )
    (net (code "43") (name "unconnected-(U1-NC-Pad5)") (class "Default")
      (node (ref "U1") (pin "5") (pinfunction "NC_5") (pintype "passive"))
    )
    (net (code "44") (name "unconnected-(U2-CHI-Pad3)") (class "Default")
      (node (ref "U2") (pin "3") (pinfunction "CHI_3") (pintype "passive"))
    )
    (net (code "45") (name "unconnected-(U3-NC-Pad1)") (class "Default")
      (node (ref "U3") (pin "1") (pinfunction "NC_1") (pintype "passive"))
    )
    (net (code "46") (name "unconnected-(U3-NC-Pad4)") (class "Default")
      (node (ref "U3") (pin "4") (pinfunction "NC_4") (pintype "passive"))
    )
    (net (code "47") (name "unconnected-(U3-NC-Pad5)") (class "Default")
      (node (ref "U3") (pin "5") (pinfunction "NC_5") (pintype "passive"))
    )
    (net (code "48") (name "unconnected-(U4-NC-Pad1)") (class "Default")
      (node (ref "U4") (pin "1") (pinfunction "NC_1") (pintype "passive"))
    )
    (net (code "49") (name "unconnected-(U4-NC-Pad4)") (class "Default")
      (node (ref "U4") (pin "4") (pinfunction "NC_4") (pintype "passive"))
    )
    (net (code "50") (name "unconnected-(U4-NC-Pad5)") (class "Default")
      (node (ref "U4") (pin "5") (pinfunction "NC_5") (pintype "passive"))
    )
  )
)
